# relais_platine_v7.net
KiCad netlist of a schematic drawn in EAGLE
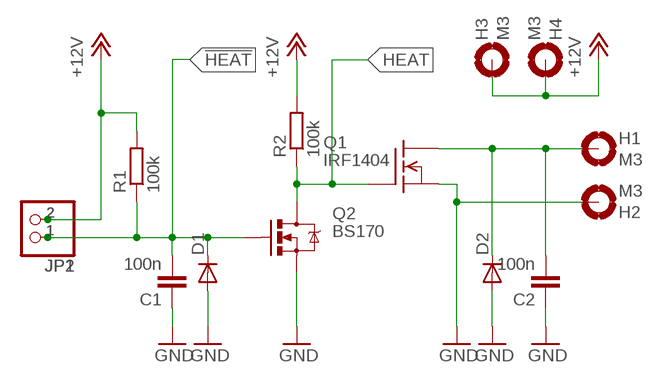
[diagram p0: schematic, sheet 1]

(export (version "E")
  (design (tool "Eeschema 10.0.6"))
  (components
    (comp (ref "C1")
      (value "100n")
      (footprint "eagle-import:C0805K")
      (libsource (lib "eagle-import") (part "C-EUC0805K"))
    )
    (comp (ref "C2")
      (value "100n")
      (footprint "eagle-import:C0805K")
      (libsource (lib "eagle-import") (part "C-EUC0805K"))
    )
    (comp (ref "D1")
      (value "DIODE-MINIMELF")
      (footprint "eagle-import:MINIMELF")
      (libsource (lib "eagle-import") (part "DIODE-MINIMELF"))
    )
    (comp (ref "D2")
      (value "DIODE-MINIMELF")
      (footprint "eagle-import:MINIMELF")
      (libsource (lib "eagle-import") (part "DIODE-MINIMELF"))
    )
    (comp (ref "H1")
      (value "M3")
      (footprint "eagle-import:3,0-PAD")
      (libsource (lib "eagle-import") (part "MOUNT-PAD-ROUND3.0"))
    )
    (comp (ref "H2")
      (value "M3")
      (footprint "eagle-import:3,0-PAD")
      (libsource (lib "eagle-import") (part "MOUNT-PAD-ROUND3.0"))
    )
    (comp (ref "H3")
      (value "M3")
      (footprint "eagle-import:3,0-PAD")
      (libsource (lib "eagle-import") (part "MOUNT-PAD-ROUND3.0"))
    )
    (comp (ref "H4")
      (value "M3")
      (footprint "eagle-import:3,0-PAD")
      (libsource (lib "eagle-import") (part "MOUNT-PAD-ROUND3.0"))
    )
    (comp (ref "JP1")
      (value "PINHD-1X2")
      (footprint "eagle-import:1X02")
      (libsource (lib "eagle-import") (part "PINHD-1X2"))
    )
    (comp (ref "JP2")
      (value "PINHD-1X2/90")
      (footprint "eagle-import:1X02_90")
      (libsource (lib "eagle-import") (part "PINHD-1X2/90"))
    )
    (comp (ref "Q1")
      (value "IRF1404")
      (footprint "eagle-import:TO220")
      (libsource (lib "eagle-import") (part "IRF540"))
    )
    (comp (ref "Q2")
      (value "BS170")
      (footprint "eagle-import:SOT23-3")
      (libsource (lib "eagle-import") (part "MOSFET-NCHANNELBSS123LT1G"))
    )
    (comp (ref "R1")
      (value "100k")
      (footprint "eagle-import:M0805")
      (libsource (lib "eagle-import") (part "R-EU_M0805"))
    )
    (comp (ref "R2")
      (value "100k")
      (footprint "eagle-import:M0805")
      (libsource (lib "eagle-import") (part "R-EU_M0805"))
    )
  )
  (nets
    (net (code "1") (name "+12V") (class "Default")
      (node (ref "H3") (pin "B3,0") (pinfunction "MOUNT_B3,0") (pintype "passive"))
      (node (ref "H4") (pin "B3,0") (pinfunction "MOUNT_B3,0") (pintype "passive"))
      (node (ref "JP1") (pin "2") (pinfunction "2_2") (pintype "passive"))
      (node (ref "JP2") (pin "2") (pinfunction "2_2") (pintype "passive"))
      (node (ref "R1") (pin "2") (pinfunction "2_2") (pintype "passive"))
      (node (ref "R2") (pin "2") (pinfunction "2_2") (pintype "passive"))
    )
    (net (code "2") (name "/~{HEAT}") (class "Default")
      (node (ref "C1") (pin "2") (pinfunction "2_2") (pintype "passive"))
      (node (ref "D1") (pin "C") (pinfunction "C_C") (pintype "passive"))
      (node (ref "JP1") (pin "1") (pinfunction "1_1") (pintype "passive"))
      (node (ref "JP2") (pin "1") (pinfunction "1_1") (pintype "passive"))
      (node (ref "Q2") (pin "1") (pinfunction "G_1") (pintype "passive"))
      (node (ref "R1") (pin "1") (pinfunction "1_1") (pintype "passive"))
    )
    (net (code "3") (name "GND") (class "Default")
      (node (ref "C1") (pin "1") (pinfunction "1_1") (pintype "passive"))
      (node (ref "C2") (pin "1") (pinfunction "1_1") (pintype "passive"))
      (node (ref "D1") (pin "A") (pinfunction "A_A") (pintype "passive"))
      (node (ref "D2") (pin "A") (pinfunction "A_A") (pintype "passive"))
      (node (ref "H2") (pin "B3,0") (pinfunction "MOUNT_B3,0") (pintype "passive"))
      (node (ref "Q1") (pin "3") (pinfunction "S_3") (pintype "passive"))
      (node (ref "Q2") (pin "2") (pinfunction "S_2") (pintype "passive"))
    )
    (net (code "4") (name "HEAT") (class "Default")
      (node (ref "Q1") (pin "1") (pinfunction "G_1") (pintype "passive"))
      (node (ref "Q2") (pin "3") (pinfunction "D_3") (pintype "passive"))
      (node (ref "R2") (pin "1") (pinfunction "1_1") (pintype "passive"))
    )
    (net (code "5") (name "Net-(H1-MOUNT)") (class "Default")
      (node (ref "C2") (pin "2") (pinfunction "2_2") (pintype "passive"))
      (node (ref "D2") (pin "C") (pinfunction "C_C") (pintype "passive"))
      (node (ref "H1") (pin "B3,0") (pinfunction "MOUNT_B3,0") (pintype "passive"))
      (node (ref "Q1") (pin "2") (pinfunction "D_2") (pintype "passive"))
    )
  )
)
